# ProProject_Shield_na_MachXO3_devboard_20.net
KiCad netlist of a schematic drawn in EasyEDA Pro
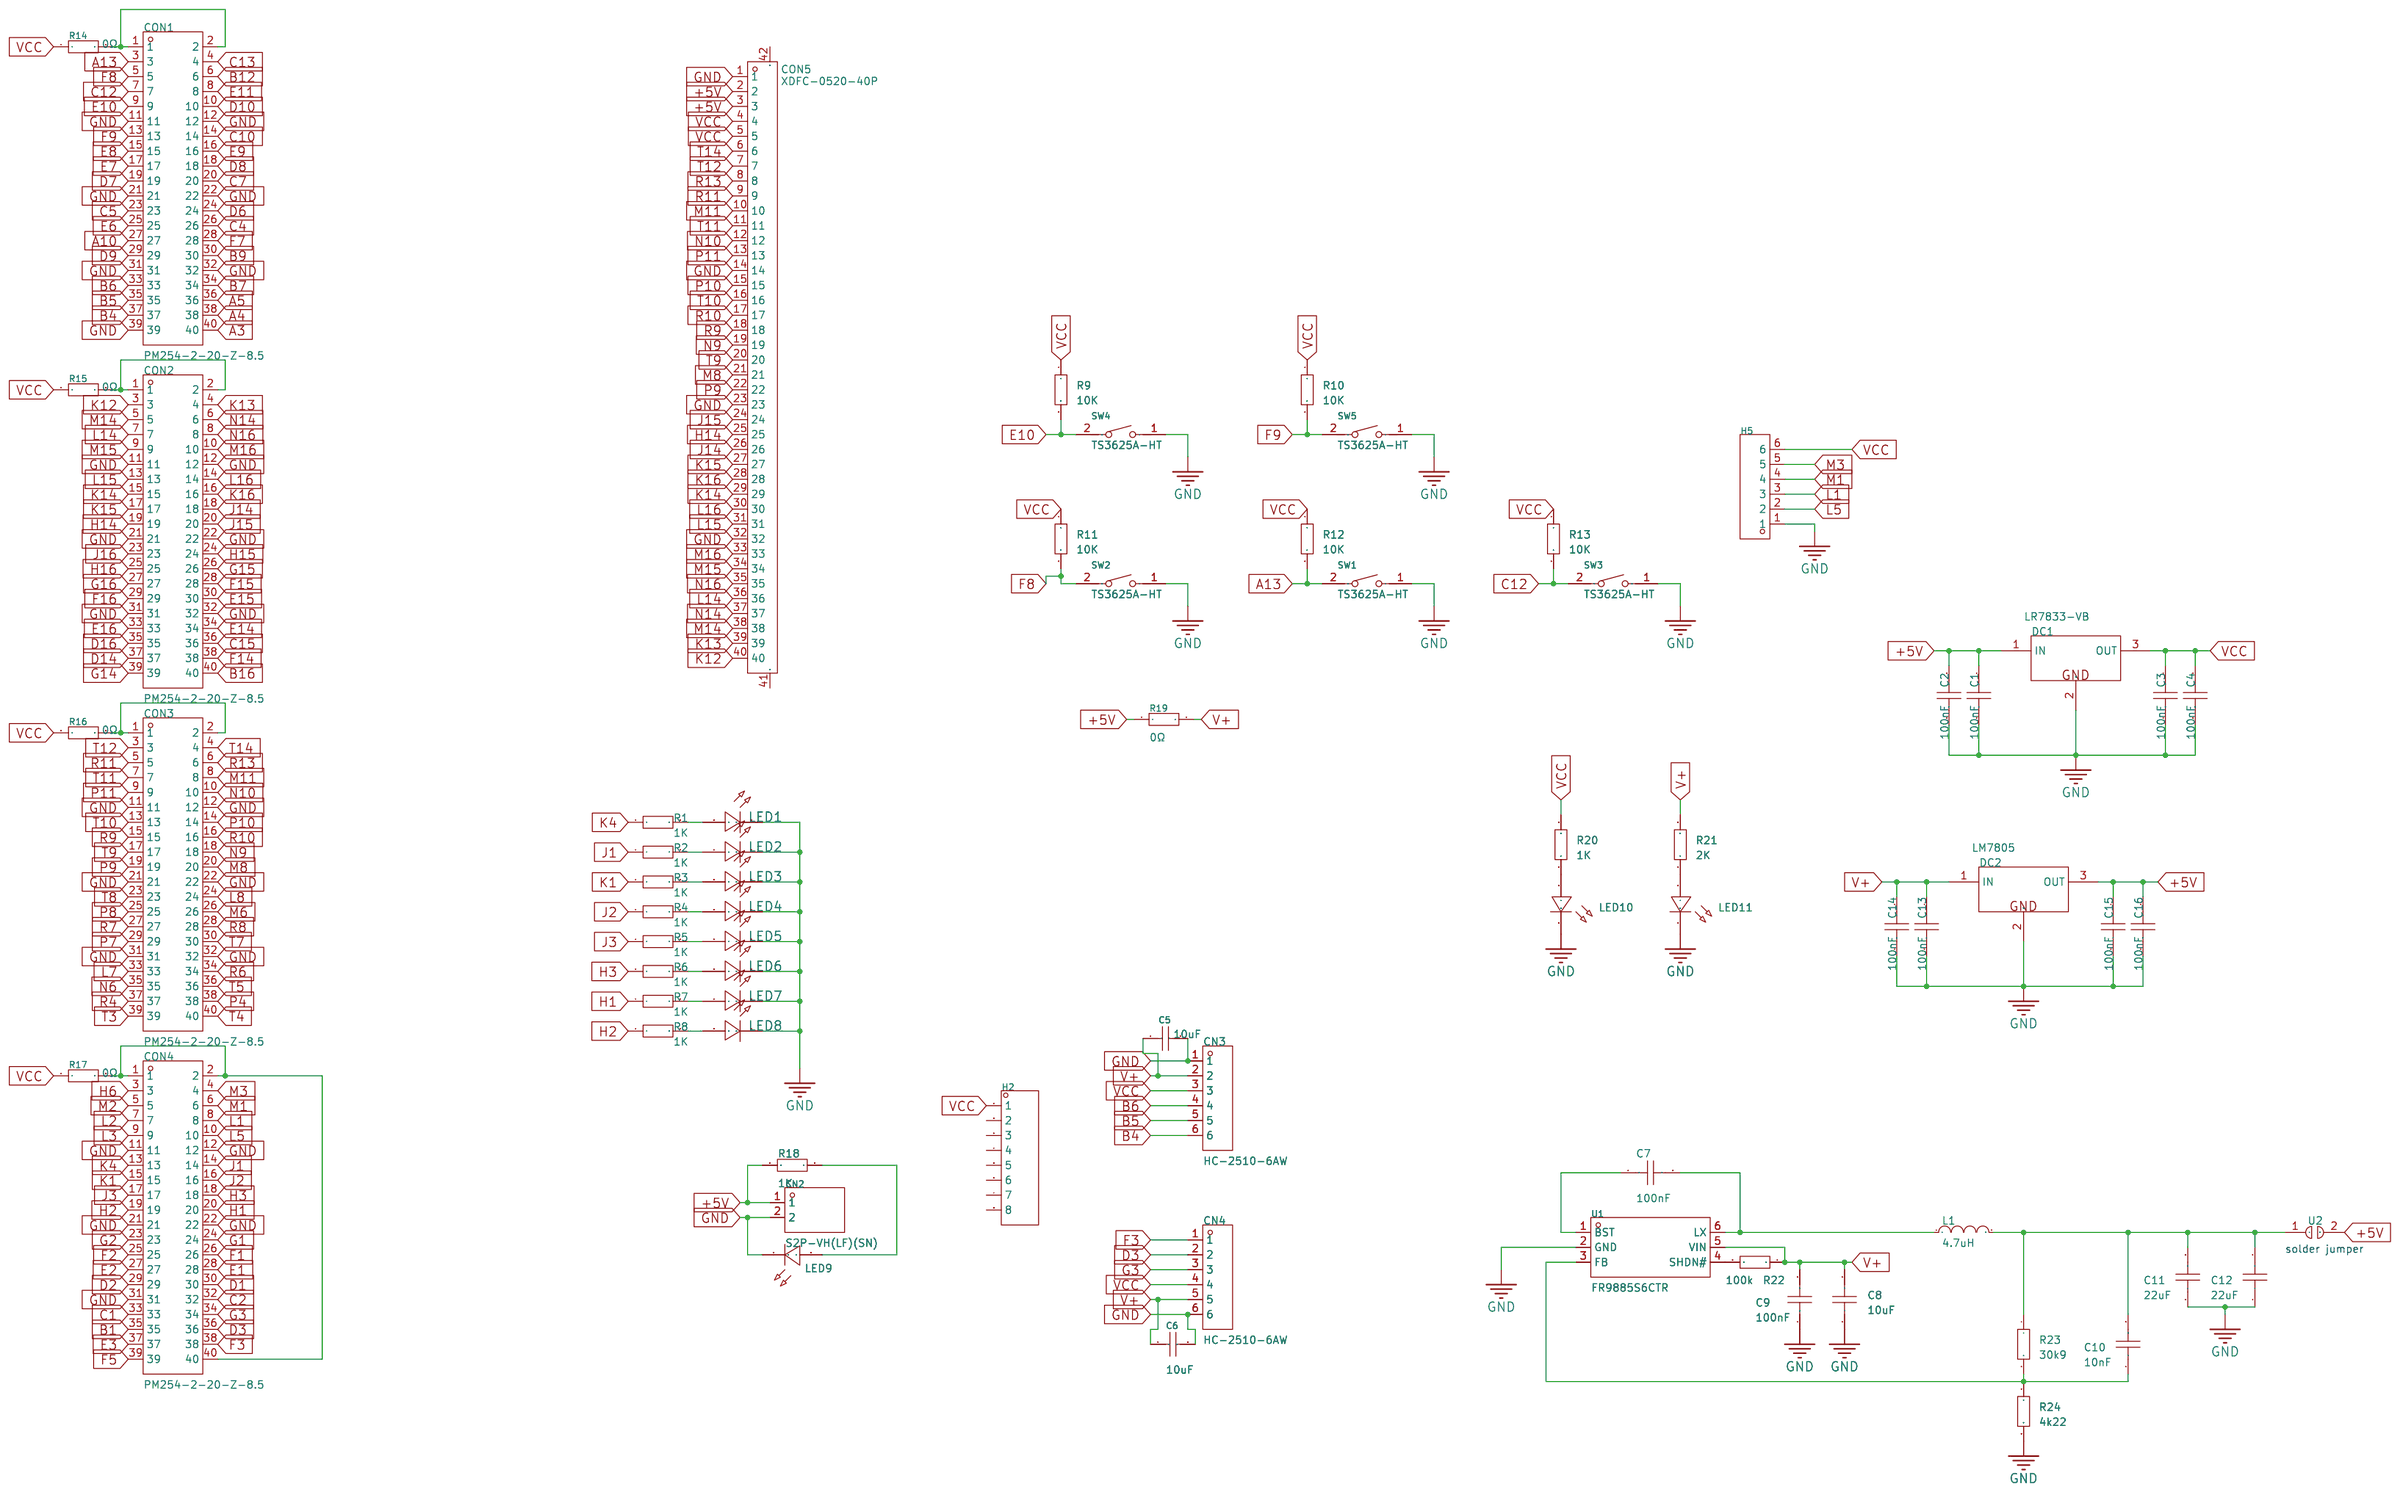
[diagram p0: schematic sheet]

(export (version "E")
  (design (tool "Eeschema 10.0.6"))
  (components
    (comp (ref "C1")
      (value "100nF")
      (footprint "easyedapro:C0805")
      (libsource (lib "easyedapro") (part "CAP"))
    )
    (comp (ref "C2")
      (value "100nF")
      (footprint "easyedapro:C0805")
      (libsource (lib "easyedapro") (part "CAP"))
    )
    (comp (ref "C3")
      (value "100nF")
      (footprint "easyedapro:C0805")
      (libsource (lib "easyedapro") (part "CAP"))
    )
    (comp (ref "C4")
      (value "100nF")
      (footprint "easyedapro:C0805")
      (libsource (lib "easyedapro") (part "CAP"))
    )
    (comp (ref "C5")
      (value "10uF")
      (footprint "easyedapro:C1206")
      (fields
        (field (name "Manufacturer Part") "CL31A107MQHNNNE")
        (field (name "Manufacturer") "SAMSUNG(三星)")
      )
      (libsource (lib "easyedapro") (part "CL31A107MQHNNNE"))
    )
    (comp (ref "C6")
      (value "10uF")
      (footprint "easyedapro:C1206")
      (fields
        (field (name "Manufacturer Part") "CL31A107MQHNNNE")
        (field (name "Manufacturer") "SAMSUNG(三星)")
      )
      (libsource (lib "easyedapro") (part "CL31A107MQHNNNE"))
    )
    (comp (ref "C7")
      (value "100nF")
      (footprint "easyedapro:C0805")
      (libsource (lib "easyedapro") (part "CAP"))
    )
    (comp (ref "C8")
      (value "10uF")
      (footprint "easyedapro:C0805")
      (libsource (lib "easyedapro") (part "CAP"))
    )
    (comp (ref "C9")
      (value "100nF")
      (footprint "easyedapro:C0805")
      (libsource (lib "easyedapro") (part "CAP"))
    )
    (comp (ref "C10")
      (value "10nF")
      (footprint "easyedapro:C0805")
      (libsource (lib "easyedapro") (part "CAP"))
    )
    (comp (ref "C11")
      (value "22uF")
      (footprint "easyedapro:C0805")
      (libsource (lib "easyedapro") (part "CAP"))
    )
    (comp (ref "C12")
      (value "22uF")
      (footprint "easyedapro:C0805")
      (libsource (lib "easyedapro") (part "CAP"))
    )
    (comp (ref "C13")
      (value "100nF")
      (footprint "easyedapro:C0805")
      (libsource (lib "easyedapro") (part "CAP"))
    )
    (comp (ref "C14")
      (value "100nF")
      (footprint "easyedapro:C0805")
      (libsource (lib "easyedapro") (part "CAP"))
    )
    (comp (ref "C15")
      (value "100nF")
      (footprint "easyedapro:C0805")
      (libsource (lib "easyedapro") (part "CAP"))
    )
    (comp (ref "C16")
      (value "100nF")
      (footprint "easyedapro:C0805")
      (libsource (lib "easyedapro") (part "CAP"))
    )
    (comp (ref "CN2")
      (value "S2P-VH(LF)(SN)")
      (footprint "easyedapro:CONN-TH_S2P-VH-LF-SN")
      (fields (field (name "Manufacturer") "JST"))
      (libsource (lib "easyedapro") (part "S2P-VH (LF)(SN)"))
    )
    (comp (ref "CN3")
      (value "HC-2510-6AW")
      (footprint "easyedapro:CONN-TH_6P-P2.54_HCTL_HC-2510-6AW")
      (fields (field (name "Manufacturer") "HCTL(华灿天禄)"))
      (libsource (lib "easyedapro") (part "HC-2510-6AW"))
    )
    (comp (ref "CN4")
      (value "HC-2510-6AW")
      (footprint "easyedapro:CONN-TH_6P-P2.54_HCTL_HC-2510-6AW")
      (fields (field (name "Manufacturer") "HCTL(华灿天禄)"))
      (libsource (lib "easyedapro") (part "HC-2510-6AW"))
    )
    (comp (ref "CON1")
      (value "PM254-2-20-Z-8.5")
      (footprint "easyedapro:HDR-TH_40P-P2.54-V-F-R2-C20-S2.54")
      (fields (field (name "Manufacturer") "HCTL(华灿天禄)"))
      (libsource (lib "easyedapro") (part "PM254-2-20-Z-8.5"))
    )
    (comp (ref "CON2")
      (value "PM254-2-20-Z-8.5")
      (footprint "easyedapro:HDR-TH_40P-P2.54-V-F-R2-C20-S2.54")
      (fields (field (name "Manufacturer") "HCTL(华灿天禄)"))
      (libsource (lib "easyedapro") (part "PM254-2-20-Z-8.5"))
    )
    (comp (ref "CON3")
      (value "PM254-2-20-Z-8.5")
      (footprint "easyedapro:HDR-TH_40P-P2.54-V-F-R2-C20-S2.54")
      (fields (field (name "Manufacturer") "HCTL(华灿天禄)"))
      (libsource (lib "easyedapro") (part "PM254-2-20-Z-8.5"))
    )
    (comp (ref "CON4")
      (value "PM254-2-20-Z-8.5")
      (footprint "easyedapro:HDR-TH_40P-P2.54-V-F-R2-C20-S2.54")
      (fields (field (name "Manufacturer") "HCTL(华灿天禄)"))
      (libsource (lib "easyedapro") (part "PM254-2-20-Z-8.5"))
    )
    (comp (ref "CON5")
      (value "XDFC-0520-40P")
      (footprint "easyedapro:FPC-SMD_40P-P0.50_XDFC-0520-40P")
      (fields (field (name "Manufacturer") "LX(连欣科技)"))
      (libsource (lib "easyedapro") (part "XDFC-0520-40P"))
    )
    (comp (ref "DC1")
      (value "LR7833-VB")
      (footprint "easyedapro:TO-252-2_L6.5-W6.1-P4.58-LS10.0-TL")
      (fields (field (name "Manufacturer") "VBsemi(微碧半导体)"))
      (libsource (lib "easyedapro") (part "L78M05ABDT-TR"))
    )
    (comp (ref "DC2")
      (value "LM7805")
      (footprint "easyedapro:TO-252-2_L6.5-W6.1-P4.58-LS10.0-TL")
      (fields (field (name "Manufacturer") "HGSEMI(华冠)"))
      (libsource (lib "easyedapro") (part "L78M05ABDT-TR"))
    )
    (comp (ref "H2")
      (value "~")
      (footprint "easyedapro:HDR-TH_8P-P2.54-V-M")
      (libsource (lib "easyedapro") (part "Header-Male-2.54_1x8"))
    )
    (comp (ref "H5")
      (value "~")
      (footprint "easyedapro:HDR-TH_6P-P2.54-V-F")
      (libsource (lib "easyedapro") (part "Header-Female-2.54_1x6"))
    )
    (comp (ref "L1")
      (value "4.7uH")
      (footprint "easyedapro:L0402")
      (libsource (lib "easyedapro") (part "电感"))
    )
    (comp (ref "LED1")
      (value "~")
      (footprint "easyedapro:LED0805-RD_GREEN")
      (libsource (lib "easyedapro") (part "LED_R"))
    )
    (comp (ref "LED2")
      (value "~")
      (footprint "easyedapro:LED0805-RD_GREEN")
      (libsource (lib "easyedapro") (part "LED_R"))
    )
    (comp (ref "LED3")
      (value "~")
      (footprint "easyedapro:LED0805-RD_GREEN")
      (libsource (lib "easyedapro") (part "LED_R"))
    )
    (comp (ref "LED4")
      (value "~")
      (footprint "easyedapro:LED0805-RD_GREEN")
      (libsource (lib "easyedapro") (part "LED_R"))
    )
    (comp (ref "LED5")
      (value "~")
      (footprint "easyedapro:LED0805-RD_GREEN")
      (libsource (lib "easyedapro") (part "LED_R"))
    )
    (comp (ref "LED6")
      (value "~")
      (footprint "easyedapro:LED0805-RD_GREEN")
      (libsource (lib "easyedapro") (part "LED_R"))
    )
    (comp (ref "LED7")
      (value "~")
      (footprint "easyedapro:LED0805-RD_GREEN")
      (libsource (lib "easyedapro") (part "LED_R"))
    )
    (comp (ref "LED8")
      (value "~")
      (footprint "easyedapro:LED0805-RD_GREEN")
      (libsource (lib "easyedapro") (part "LED_R"))
    )
    (comp (ref "LED9")
      (value "~")
      (footprint "easyedapro:LED0805-RD_GREEN")
      (libsource (lib "easyedapro") (part "LED_G"))
    )
    (comp (ref "LED10")
      (value "~")
      (footprint "easyedapro:LED0805-RD_GREEN")
      (libsource (lib "easyedapro") (part "LED_B"))
    )
    (comp (ref "LED11")
      (value "~")
      (footprint "easyedapro:LED0805-RD_GREEN")
      (libsource (lib "easyedapro") (part "LED_G"))
    )
    (comp (ref "R1") (value "1K") (footprint "easyedapro:R0201") (libsource (lib "easyedapro") (part "Res")))
    (comp (ref "R2") (value "1K") (footprint "easyedapro:R0201") (libsource (lib "easyedapro") (part "Res")))
    (comp (ref "R3") (value "1K") (footprint "easyedapro:R0201") (libsource (lib "easyedapro") (part "Res")))
    (comp (ref "R4") (value "1K") (footprint "easyedapro:R0201") (libsource (lib "easyedapro") (part "Res")))
    (comp (ref "R5") (value "1K") (footprint "easyedapro:R0201") (libsource (lib "easyedapro") (part "Res")))
    (comp (ref "R6") (value "1K") (footprint "easyedapro:R0201") (libsource (lib "easyedapro") (part "Res")))
    (comp (ref "R7") (value "1K") (footprint "easyedapro:R0201") (libsource (lib "easyedapro") (part "Res")))
    (comp (ref "R8") (value "1K") (footprint "easyedapro:R0201") (libsource (lib "easyedapro") (part "Res")))
    (comp (ref "R9") (value "10K") (footprint "easyedapro:R0201") (libsource (lib "easyedapro") (part "Res")))
    (comp (ref "R10")
      (value "10K")
      (footprint "easyedapro:R0201")
      (libsource (lib "easyedapro") (part "Res"))
    )
    (comp (ref "R11")
      (value "10K")
      (footprint "easyedapro:R0201")
      (libsource (lib "easyedapro") (part "Res"))
    )
    (comp (ref "R12")
      (value "10K")
      (footprint "easyedapro:R0201")
      (libsource (lib "easyedapro") (part "Res"))
    )
    (comp (ref "R13")
      (value "10K")
      (footprint "easyedapro:R0201")
      (libsource (lib "easyedapro") (part "Res"))
    )
    (comp (ref "R14")
      (value "0Ω")
      (footprint "easyedapro:R0805")
      (fields
        (field (name "Manufacturer Part") "0805W8F0000T5E")
        (field (name "Manufacturer") "UNI-ROYAL(厚声)")
      )
      (libsource (lib "easyedapro") (part "0805W8F0000T5E"))
    )
    (comp (ref "R15")
      (value "0Ω")
      (footprint "easyedapro:R0805")
      (fields
        (field (name "Manufacturer Part") "0805W8F0000T5E")
        (field (name "Manufacturer") "UNI-ROYAL(厚声)")
      )
      (libsource (lib "easyedapro") (part "0805W8F0000T5E"))
    )
    (comp (ref "R16")
      (value "0Ω")
      (footprint "easyedapro:R0805")
      (fields
        (field (name "Manufacturer Part") "0805W8F0000T5E")
        (field (name "Manufacturer") "UNI-ROYAL(厚声)")
      )
      (libsource (lib "easyedapro") (part "0805W8F0000T5E"))
    )
    (comp (ref "R17")
      (value "0Ω")
      (footprint "easyedapro:R0805")
      (fields
        (field (name "Manufacturer Part") "0805W8F0000T5E")
        (field (name "Manufacturer") "UNI-ROYAL(厚声)")
      )
      (libsource (lib "easyedapro") (part "0805W8F0000T5E"))
    )
    (comp (ref "R18") (value "1K") (footprint "easyedapro:R0201") (libsource (lib "easyedapro") (part "Res")))
    (comp (ref "R19")
      (value "0Ω")
      (footprint "easyedapro:R0805")
      (fields
        (field (name "Manufacturer Part") "0805W8F0000T5E")
        (field (name "Manufacturer") "UNI-ROYAL(厚声)")
      )
      (libsource (lib "easyedapro") (part "0805W8F0000T5E"))
    )
    (comp (ref "R20") (value "1K") (footprint "easyedapro:R0201") (libsource (lib "easyedapro") (part "Res")))
    (comp (ref "R21") (value "2K") (footprint "easyedapro:R0201") (libsource (lib "easyedapro") (part "Res")))
    (comp (ref "R22")
      (value "100k")
      (footprint "easyedapro:R0201")
      (libsource (lib "easyedapro") (part "Res"))
    )
    (comp (ref "R23")
      (value "30k9")
      (footprint "easyedapro:R0201")
      (libsource (lib "easyedapro") (part "Res"))
    )
    (comp (ref "R24")
      (value "4k22")
      (footprint "easyedapro:R0201")
      (libsource (lib "easyedapro") (part "Res"))
    )
    (comp (ref "SW1")
      (value "TS3625A-HT")
      (footprint "easyedapro:SW-SMD_L6.1-W3.7-LS7.9")
      (fields (field (name "Manufacturer") "SHOU HAN(首韩)"))
      (libsource (lib "easyedapro") (part "TS3625A-HT"))
    )
    (comp (ref "SW2")
      (value "TS3625A-HT")
      (footprint "easyedapro:SW-SMD_L6.1-W3.7-LS7.9")
      (fields (field (name "Manufacturer") "SHOU HAN(首韩)"))
      (libsource (lib "easyedapro") (part "TS3625A-HT"))
    )
    (comp (ref "SW3")
      (value "TS3625A-HT")
      (footprint "easyedapro:SW-SMD_L6.1-W3.7-LS7.9")
      (fields (field (name "Manufacturer") "SHOU HAN(首韩)"))
      (libsource (lib "easyedapro") (part "TS3625A-HT"))
    )
    (comp (ref "SW4")
      (value "TS3625A-HT")
      (footprint "easyedapro:SW-SMD_L6.1-W3.7-LS7.9")
      (fields (field (name "Manufacturer") "SHOU HAN(首韩)"))
      (libsource (lib "easyedapro") (part "TS3625A-HT"))
    )
    (comp (ref "SW5")
      (value "TS3625A-HT")
      (footprint "easyedapro:SW-SMD_L6.1-W3.7-LS7.9")
      (fields (field (name "Manufacturer") "SHOU HAN(首韩)"))
      (libsource (lib "easyedapro") (part "TS3625A-HT"))
    )
    (comp (ref "U1")
      (value "FR9885S6CTR")
      (footprint "easyedapro:SOT-23-6_L2.9-W1.6-P0.95-LS2.8-BR")
      (fields (field (name "Manufacturer") "FITIPOWER(天钰)"))
      (libsource (lib "easyedapro") (part "FR9885S6CTR"))
    )
    (comp (ref "U2")
      (value "~")
      (footprint "easyedapro:Jumper")
      (libsource (lib "easyedapro") (part "Jumper"))
    )
  )
  (nets
    (net (code "1") (name "+5V") (class "Default")
      (node (ref "C1") (pin "1") (pinfunction "1_1") (pintype "input"))
      (node (ref "C15") (pin "1") (pinfunction "1_1") (pintype "input"))
      (node (ref "C16") (pin "1") (pinfunction "1_1") (pintype "input"))
      (node (ref "C2") (pin "1") (pinfunction "1_1") (pintype "input"))
      (node (ref "CN2") (pin "1") (pinfunction "1_1") (pintype "input"))
      (node (ref "CON5") (pin "2") (pinfunction "2_2") (pintype "unspecified"))
      (node (ref "CON5") (pin "3") (pinfunction "3_3") (pintype "unspecified"))
      (node (ref "DC1") (pin "1") (pinfunction "IN_1") (pintype "unspecified"))
      (node (ref "DC2") (pin "3") (pinfunction "OUT_3") (pintype "unspecified"))
      (node (ref "R18") (pin "1") (pinfunction "1_1") (pintype "input"))
      (node (ref "R19") (pin "1") (pinfunction "1_1") (pintype "input"))
      (node (ref "U2") (pin "2") (pinfunction "2_2") (pintype "input"))
    )
    (net (code "2") (name "A3") (class "Default")
      (node (ref "CON1") (pin "40") (pinfunction "40_40") (pintype "unspecified"))
    )
    (net (code "3") (name "A4") (class "Default")
      (node (ref "CON1") (pin "38") (pinfunction "38_38") (pintype "unspecified"))
    )
    (net (code "4") (name "A5") (class "Default")
      (node (ref "CON1") (pin "36") (pinfunction "36_36") (pintype "unspecified"))
    )
    (net (code "5") (name "A10") (class "Default")
      (node (ref "CON1") (pin "27") (pinfunction "27_27") (pintype "unspecified"))
    )
    (net (code "6") (name "A13") (class "Default")
      (node (ref "CON1") (pin "3") (pinfunction "3_3") (pintype "unspecified"))
      (node (ref "R12") (pin "2") (pinfunction "2_2") (pintype "input"))
      (node (ref "SW1") (pin "2") (pinfunction "B_2") (pintype "input"))
    )
    (net (code "7") (name "B1") (class "Default")
      (node (ref "CON4") (pin "35") (pinfunction "35_35") (pintype "unspecified"))
    )
    (net (code "8") (name "B4") (class "Default")
      (node (ref "CN3") (pin "6") (pinfunction "6_6") (pintype "unspecified"))
      (node (ref "CON1") (pin "37") (pinfunction "37_37") (pintype "unspecified"))
    )
    (net (code "9") (name "B5") (class "Default")
      (node (ref "CN3") (pin "5") (pinfunction "5_5") (pintype "unspecified"))
      (node (ref "CON1") (pin "35") (pinfunction "35_35") (pintype "unspecified"))
    )
    (net (code "10") (name "B6") (class "Default")
      (node (ref "CN3") (pin "4") (pinfunction "4_4") (pintype "unspecified"))
      (node (ref "CON1") (pin "33") (pinfunction "33_33") (pintype "unspecified"))
    )
    (net (code "11") (name "B7") (class "Default")
      (node (ref "CON1") (pin "34") (pinfunction "34_34") (pintype "unspecified"))
    )
    (net (code "12") (name "B9") (class "Default")
      (node (ref "CON1") (pin "30") (pinfunction "30_30") (pintype "unspecified"))
    )
    (net (code "13") (name "B12") (class "Default")
      (node (ref "CON1") (pin "6") (pinfunction "6_6") (pintype "unspecified"))
    )
    (net (code "14") (name "B16") (class "Default")
      (node (ref "CON2") (pin "40") (pinfunction "40_40") (pintype "unspecified"))
    )
    (net (code "15") (name "C1") (class "Default")
      (node (ref "CON4") (pin "33") (pinfunction "33_33") (pintype "unspecified"))
    )
    (net (code "16") (name "C2") (class "Default")
      (node (ref "CON4") (pin "32") (pinfunction "32_32") (pintype "unspecified"))
    )
    (net (code "17") (name "C4") (class "Default")
      (node (ref "CON1") (pin "26") (pinfunction "26_26") (pintype "unspecified"))
    )
    (net (code "18") (name "C5") (class "Default")
      (node (ref "CON1") (pin "23") (pinfunction "23_23") (pintype "unspecified"))
    )
    (net (code "19") (name "C7") (class "Default")
      (node (ref "CON1") (pin "20") (pinfunction "20_20") (pintype "unspecified"))
    )
    (net (code "20") (name "C10") (class "Default")
      (node (ref "CON1") (pin "14") (pinfunction "14_14") (pintype "unspecified"))
    )
    (net (code "21") (name "C12") (class "Default")
      (node (ref "CON1") (pin "7") (pinfunction "7_7") (pintype "unspecified"))
      (node (ref "R13") (pin "2") (pinfunction "2_2") (pintype "input"))
      (node (ref "SW3") (pin "2") (pinfunction "B_2") (pintype "input"))
    )
    (net (code "22") (name "C13") (class "Default")
      (node (ref "CON1") (pin "4") (pinfunction "4_4") (pintype "unspecified"))
    )
    (net (code "23") (name "C15") (class "Default")
      (node (ref "CON2") (pin "36") (pinfunction "36_36") (pintype "unspecified"))
    )
    (net (code "24") (name "D1") (class "Default")
      (node (ref "CON4") (pin "30") (pinfunction "30_30") (pintype "unspecified"))
    )
    (net (code "25") (name "D2") (class "Default")
      (node (ref "CON4") (pin "29") (pinfunction "29_29") (pintype "unspecified"))
    )
    (net (code "26") (name "D3") (class "Default")
      (node (ref "CN4") (pin "2") (pinfunction "2_2") (pintype "unspecified"))
      (node (ref "CON4") (pin "36") (pinfunction "36_36") (pintype "unspecified"))
    )
    (net (code "27") (name "D6") (class "Default")
      (node (ref "CON1") (pin "24") (pinfunction "24_24") (pintype "unspecified"))
    )
    (net (code "28") (name "D7") (class "Default")
      (node (ref "CON1") (pin "19") (pinfunction "19_19") (pintype "unspecified"))
    )
    (net (code "29") (name "D8") (class "Default")
      (node (ref "CON1") (pin "18") (pinfunction "18_18") (pintype "unspecified"))
    )
    (net (code "30") (name "D9") (class "Default")
      (node (ref "CON1") (pin "29") (pinfunction "29_29") (pintype "unspecified"))
    )
    (net (code "31") (name "D10") (class "Default")
      (node (ref "CON1") (pin "10") (pinfunction "10_10") (pintype "unspecified"))
    )
    (net (code "32") (name "D14") (class "Default")
      (node (ref "CON2") (pin "37") (pinfunction "37_37") (pintype "unspecified"))
    )
    (net (code "33") (name "D16") (class "Default")
      (node (ref "CON2") (pin "35") (pinfunction "35_35") (pintype "unspecified"))
    )
    (net (code "34") (name "E1") (class "Default")
      (node (ref "CON4") (pin "28") (pinfunction "28_28") (pintype "unspecified"))
    )
    (net (code "35") (name "E2") (class "Default")
      (node (ref "CON4") (pin "27") (pinfunction "27_27") (pintype "unspecified"))
    )
    (net (code "36") (name "E3") (class "Default")
      (node (ref "CON4") (pin "37") (pinfunction "37_37") (pintype "unspecified"))
    )
    (net (code "37") (name "E6") (class "Default")
      (node (ref "CON1") (pin "25") (pinfunction "25_25") (pintype "unspecified"))
    )
    (net (code "38") (name "E7") (class "Default")
      (node (ref "CON1") (pin "17") (pinfunction "17_17") (pintype "unspecified"))
    )
    (net (code "39") (name "E8") (class "Default")
      (node (ref "CON1") (pin "15") (pinfunction "15_15") (pintype "unspecified"))
    )
    (net (code "40") (name "E9") (class "Default")
      (node (ref "CON1") (pin "16") (pinfunction "16_16") (pintype "unspecified"))
    )
    (net (code "41") (name "E10") (class "Default")
      (node (ref "CON1") (pin "9") (pinfunction "9_9") (pintype "unspecified"))
      (node (ref "R9") (pin "2") (pinfunction "2_2") (pintype "input"))
      (node (ref "SW4") (pin "2") (pinfunction "B_2") (pintype "input"))
    )
    (net (code "42") (name "E11") (class "Default")
      (node (ref "CON1") (pin "8") (pinfunction "8_8") (pintype "unspecified"))
    )
    (net (code "43") (name "E14") (class "Default")
      (node (ref "CON2") (pin "34") (pinfunction "34_34") (pintype "unspecified"))
    )
    (net (code "44") (name "E15") (class "Default")
      (node (ref "CON2") (pin "30") (pinfunction "30_30") (pintype "unspecified"))
    )
    (net (code "45") (name "E16") (class "Default")
      (node (ref "CON2") (pin "33") (pinfunction "33_33") (pintype "unspecified"))
    )
    (net (code "46") (name "F1") (class "Default")
      (node (ref "CON4") (pin "26") (pinfunction "26_26") (pintype "unspecified"))
    )
    (net (code "47") (name "F2") (class "Default")
      (node (ref "CON4") (pin "25") (pinfunction "25_25") (pintype "unspecified"))
    )
    (net (code "48") (name "F3") (class "Default")
      (node (ref "CN4") (pin "1") (pinfunction "1_1") (pintype "unspecified"))
      (node (ref "CON4") (pin "38") (pinfunction "38_38") (pintype "unspecified"))
    )
    (net (code "49") (name "F5") (class "Default")
      (node (ref "CON4") (pin "39") (pinfunction "39_39") (pintype "unspecified"))
    )
    (net (code "50") (name "F7") (class "Default")
      (node (ref "CON1") (pin "28") (pinfunction "28_28") (pintype "unspecified"))
    )
    (net (code "51") (name "F8") (class "Default")
      (node (ref "CON1") (pin "5") (pinfunction "5_5") (pintype "unspecified"))
      (node (ref "R11") (pin "2") (pinfunction "2_2") (pintype "input"))
      (node (ref "SW2") (pin "2") (pinfunction "B_2") (pintype "input"))
    )
    (net (code "52") (name "F9") (class "Default")
      (node (ref "CON1") (pin "13") (pinfunction "13_13") (pintype "unspecified"))
      (node (ref "R10") (pin "2") (pinfunction "2_2") (pintype "input"))
      (node (ref "SW5") (pin "2") (pinfunction "B_2") (pintype "input"))
    )
    (net (code "53") (name "F14") (class "Default")
      (node (ref "CON2") (pin "38") (pinfunction "38_38") (pintype "unspecified"))
    )
    (net (code "54") (name "F15") (class "Default")
      (node (ref "CON2") (pin "28") (pinfunction "28_28") (pintype "unspecified"))
    )
    (net (code "55") (name "F16") (class "Default")
      (node (ref "CON2") (pin "29") (pinfunction "29_29") (pintype "unspecified"))
    )
    (net (code "56") (name "G1") (class "Default")
      (node (ref "CON4") (pin "24") (pinfunction "24_24") (pintype "unspecified"))
    )
    (net (code "57") (name "G2") (class "Default")
      (node (ref "CON4") (pin "23") (pinfunction "23_23") (pintype "unspecified"))
    )
    (net (code "58") (name "G3") (class "Default")
      (node (ref "CN4") (pin "3") (pinfunction "3_3") (pintype "unspecified"))
      (node (ref "CON4") (pin "34") (pinfunction "34_34") (pintype "unspecified"))
    )
    (net (code "59") (name "G14") (class "Default")
      (node (ref "CON2") (pin "39") (pinfunction "39_39") (pintype "unspecified"))
    )
    (net (code "60") (name "G15") (class "Default")
      (node (ref "CON2") (pin "26") (pinfunction "26_26") (pintype "unspecified"))
    )
    (net (code "61") (name "G16") (class "Default")
      (node (ref "CON2") (pin "27") (pinfunction "27_27") (pintype "unspecified"))
    )
    (net (code "62") (name "GND") (class "Default")
      (node (ref "C1") (pin "2") (pinfunction "2_2") (pintype "input"))
      (node (ref "C11") (pin "1") (pinfunction "1_1") (pintype "input"))
      (node (ref "C12") (pin "1") (pinfunction "1_1") (pintype "input"))
      (node (ref "C13") (pin "2") (pinfunction "2_2") (pintype "input"))
      (node (ref "C14") (pin "2") (pinfunction "2_2") (pintype "input"))
      (node (ref "C15") (pin "2") (pinfunction "2_2") (pintype "input"))
      (node (ref "C16") (pin "2") (pinfunction "2_2") (pintype "input"))
      (node (ref "C2") (pin "2") (pinfunction "2_2") (pintype "input"))
      (node (ref "C3") (pin "2") (pinfunction "2_2") (pintype "input"))
      (node (ref "C4") (pin "2") (pinfunction "2_2") (pintype "input"))
      (node (ref "C5") (pin "2") (pinfunction "2_2") (pintype "input"))
      (node (ref "C6") (pin "2") (pinfunction "2_2") (pintype "input"))
      (node (ref "C8") (pin "1") (pinfunction "1_1") (pintype "input"))
      (node (ref "C9") (pin "1") (pinfunction "1_1") (pintype "input"))
      (node (ref "CN2") (pin "2") (pinfunction "2_2") (pintype "input"))
      (node (ref "CN3") (pin "1") (pinfunction "1_1") (pintype "unspecified"))
      (node (ref "CN4") (pin "6") (pinfunction "6_6") (pintype "unspecified"))
      (node (ref "CON1") (pin "11") (pinfunction "11_11") (pintype "unspecified"))
      (node (ref "CON1") (pin "12") (pinfunction "12_12") (pintype "unspecified"))
      (node (ref "CON1") (pin "21") (pinfunction "21_21") (pintype "unspecified"))
      (node (ref "CON1") (pin "22") (pinfunction "22_22") (pintype "unspecified"))
      (node (ref "CON1") (pin "31") (pinfunction "31_31") (pintype "unspecified"))
      (node (ref "CON1") (pin "32") (pinfunction "32_32") (pintype "unspecified"))
      (node (ref "CON1") (pin "39") (pinfunction "39_39") (pintype "unspecified"))
      (node (ref "CON2") (pin "11") (pinfunction "11_11") (pintype "unspecified"))
      (node (ref "CON2") (pin "12") (pinfunction "12_12") (pintype "unspecified"))
      (node (ref "CON2") (pin "21") (pinfunction "21_21") (pintype "unspecified"))
      (node (ref "CON2") (pin "22") (pinfunction "22_22") (pintype "unspecified"))
      (node (ref "CON2") (pin "31") (pinfunction "31_31") (pintype "unspecified"))
      (node (ref "CON2") (pin "32") (pinfunction "32_32") (pintype "unspecified"))
      (node (ref "CON3") (pin "11") (pinfunction "11_11") (pintype "unspecified"))
      (node (ref "CON3") (pin "12") (pinfunction "12_12") (pintype "unspecified"))
      (node (ref "CON3") (pin "21") (pinfunction "21_21") (pintype "unspecified"))
      (node (ref "CON3") (pin "22") (pinfunction "22_22") (pintype "unspecified"))
      (node (ref "CON3") (pin "31") (pinfunction "31_31") (pintype "unspecified"))
      (node (ref "CON3") (pin "32") (pinfunction "32_32") (pintype "unspecified"))
      (node (ref "CON4") (pin "11") (pinfunction "11_11") (pintype "unspecified"))
      (node (ref "CON4") (pin "12") (pinfunction "12_12") (pintype "unspecified"))
      (node (ref "CON4") (pin "21") (pinfunction "21_21") (pintype "unspecified"))
      (node (ref "CON4") (pin "22") (pinfunction "22_22") (pintype "unspecified"))
      (node (ref "CON4") (pin "31") (pinfunction "31_31") (pintype "unspecified"))
      (node (ref "CON5") (pin "1") (pinfunction "1_1") (pintype "unspecified"))
      (node (ref "CON5") (pin "14") (pinfunction "14_14") (pintype "unspecified"))
      (node (ref "CON5") (pin "23") (pinfunction "23_23") (pintype "unspecified"))
      (node (ref "CON5") (pin "32") (pinfunction "32_32") (pintype "unspecified"))
      (node (ref "DC1") (pin "2") (pinfunction "GND_2") (pintype "unspecified"))
      (node (ref "DC2") (pin "2") (pinfunction "GND_2") (pintype "unspecified"))
      (node (ref "H5") (pin "1") (pinfunction "1_1") (pintype "input"))
      (node (ref "LED1") (pin "2") (pinfunction "C_2") (pintype "input"))
      (node (ref "LED10") (pin "1") (pinfunction "C_1") (pintype "input"))
      (node (ref "LED11") (pin "1") (pinfunction "C_1") (pintype "input"))
      (node (ref "LED2") (pin "2") (pinfunction "C_2") (pintype "input"))
      (node (ref "LED3") (pin "2") (pinfunction "C_2") (pintype "input"))
      (node (ref "LED4") (pin "2") (pinfunction "C_2") (pintype "input"))
      (node (ref "LED5") (pin "2") (pinfunction "C_2") (pintype "input"))
      (node (ref "LED6") (pin "2") (pinfunction "C_2") (pintype "input"))
      (node (ref "LED7") (pin "2") (pinfunction "C_2") (pintype "input"))
      (node (ref "LED8") (pin "2") (pinfunction "C_2") (pintype "input"))
      (node (ref "LED9") (pin "1") (pinfunction "C_1") (pintype "input"))
      (node (ref "R24") (pin "2") (pinfunction "2_2") (pintype "input"))
      (node (ref "SW1") (pin "1") (pinfunction "A_1") (pintype "input"))
      (node (ref "SW2") (pin "1") (pinfunction "A_1") (pintype "input"))
      (node (ref "SW3") (pin "1") (pinfunction "A_1") (pintype "input"))
      (node (ref "SW4") (pin "1") (pinfunction "A_1") (pintype "input"))
      (node (ref "SW5") (pin "1") (pinfunction "A_1") (pintype "input"))
      (node (ref "U1") (pin "2") (pinfunction "GND_2") (pintype "input"))
    )
    (net (code "63") (name "H1") (class "Default")
      (node (ref "CON4") (pin "20") (pinfunction "20_20") (pintype "unspecified"))
      (node (ref "R7") (pin "1") (pinfunction "1_1") (pintype "input"))
    )
    (net (code "64") (name "H2") (class "Default")
      (node (ref "CON4") (pin "19") (pinfunction "19_19") (pintype "unspecified"))
      (node (ref "R8") (pin "1") (pinfunction "1_1") (pintype "input"))
    )
    (net (code "65") (name "H3") (class "Default")
      (node (ref "CON4") (pin "18") (pinfunction "18_18") (pintype "unspecified"))
      (node (ref "R6") (pin "1") (pinfunction "1_1") (pintype "input"))
    )
    (net (code "66") (name "H6") (class "Default")
      (node (ref "CON4") (pin "3") (pinfunction "3_3") (pintype "unspecified"))
    )
    (net (code "67") (name "H14") (class "Default")
      (node (ref "CON2") (pin "19") (pinfunction "19_19") (pintype "unspecified"))
      (node (ref "CON5") (pin "25") (pinfunction "25_25") (pintype "unspecified"))
    )
    (net (code "68") (name "H15") (class "Default")
      (node (ref "CON2") (pin "24") (pinfunction "24_24") (pintype "unspecified"))
    )
    (net (code "69") (name "H16") (class "Default")
      (node (ref "CON2") (pin "25") (pinfunction "25_25") (pintype "unspecified"))
    )
    (net (code "70") (name "J1") (class "Default")
      (node (ref "CON4") (pin "14") (pinfunction "14_14") (pintype "unspecified"))
      (node (ref "R2") (pin "1") (pinfunction "1_1") (pintype "input"))
    )
    (net (code "71") (name "J2") (class "Default")
      (node (ref "CON4") (pin "16") (pinfunction "16_16") (pintype "unspecified"))
      (node (ref "R4") (pin "1") (pinfunction "1_1") (pintype "input"))
    )
    (net (code "72") (name "J3") (class "Default")
      (node (ref "CON4") (pin "17") (pinfunction "17_17") (pintype "unspecified"))
      (node (ref "R5") (pin "1") (pinfunction "1_1") (pintype "input"))
    )
    (net (code "73") (name "J14") (class "Default")
      (node (ref "CON2") (pin "18") (pinfunction "18_18") (pintype "unspecified"))
      (node (ref "CON5") (pin "26") (pinfunction "26_26") (pintype "unspecified"))
    )
    (net (code "74") (name "J15") (class "Default")
      (node (ref "CON2") (pin "20") (pinfunction "20_20") (pintype "unspecified"))
      (node (ref "CON5") (pin "24") (pinfunction "24_24") (pintype "unspecified"))
    )
    (net (code "75") (name "J16") (class "Default")
      (node (ref "CON2") (pin "23") (pinfunction "23_23") (pintype "unspecified"))
    )
    (net (code "76") (name "K1") (class "Default")
      (node (ref "CON4") (pin "15") (pinfunction "15_15") (pintype "unspecified"))
      (node (ref "R3") (pin "1") (pinfunction "1_1") (pintype "input"))
    )
    (net (code "77") (name "K4") (class "Default")
      (node (ref "CON4") (pin "13") (pinfunction "13_13") (pintype "unspecified"))
      (node (ref "R1") (pin "1") (pinfunction "1_1") (pintype "input"))
    )
    (net (code "78") (name "K12") (class "Default")
      (node (ref "CON2") (pin "3") (pinfunction "3_3") (pintype "unspecified"))
      (node (ref "CON5") (pin "40") (pinfunction "40_40") (pintype "unspecified"))
    )
    (net (code "79") (name "K13") (class "Default")
      (node (ref "CON2") (pin "4") (pinfunction "4_4") (pintype "unspecified"))
      (node (ref "CON5") (pin "39") (pinfunction "39_39") (pintype "unspecified"))
    )
    (net (code "80") (name "K14") (class "Default")
      (node (ref "CON2") (pin "15") (pinfunction "15_15") (pintype "unspecified"))
      (node (ref "CON5") (pin "29") (pinfunction "29_29") (pintype "unspecified"))
    )
    (net (code "81") (name "K15") (class "Default")
      (node (ref "CON2") (pin "17") (pinfunction "17_17") (pintype "unspecified"))
      (node (ref "CON5") (pin "27") (pinfunction "27_27") (pintype "unspecified"))
    )
    (net (code "82") (name "K16") (class "Default")
      (node (ref "CON2") (pin "16") (pinfunction "16_16") (pintype "unspecified"))
      (node (ref "CON5") (pin "28") (pinfunction "28_28") (pintype "unspecified"))
    )
    (net (code "83") (name "L1") (class "Default")
      (node (ref "CON4") (pin "8") (pinfunction "8_8") (pintype "unspecified"))
      (node (ref "H5") (pin "3") (pinfunction "3_3") (pintype "input"))
    )
    (net (code "84") (name "L2") (class "Default")
      (node (ref "CON4") (pin "7") (pinfunction "7_7") (pintype "unspecified"))
    )
    (net (code "85") (name "L3") (class "Default")
      (node (ref "CON4") (pin "9") (pinfunction "9_9") (pintype "unspecified"))
    )
    (net (code "86") (name "L5") (class "Default")
      (node (ref "CON4") (pin "10") (pinfunction "10_10") (pintype "unspecified"))
      (node (ref "H5") (pin "2") (pinfunction "2_2") (pintype "input"))
    )
    (net (code "87") (name "L7") (class "Default")
      (node (ref "CON3") (pin "33") (pinfunction "33_33") (pintype "unspecified"))
    )
    (net (code "88") (name "L8") (class "Default")
      (node (ref "CON3") (pin "24") (pinfunction "24_24") (pintype "unspecified"))
    )
    (net (code "89") (name "L14") (class "Default")
      (node (ref "CON2") (pin "7") (pinfunction "7_7") (pintype "unspecified"))
      (node (ref "CON5") (pin "36") (pinfunction "36_36") (pintype "unspecified"))
    )
    (net (code "90") (name "L15") (class "Default")
      (node (ref "CON2") (pin "13") (pinfunction "13_13") (pintype "unspecified"))
      (node (ref "CON5") (pin "31") (pinfunction "31_31") (pintype "unspecified"))
    )
    (net (code "91") (name "L16") (class "Default")
      (node (ref "CON2") (pin "14") (pinfunction "14_14") (pintype "unspecified"))
      (node (ref "CON5") (pin "30") (pinfunction "30_30") (pintype "unspecified"))
    )
    (net (code "92") (name "M1") (class "Default")
      (node (ref "CON4") (pin "6") (pinfunction "6_6") (pintype "unspecified"))
      (node (ref "H5") (pin "4") (pinfunction "4_4") (pintype "input"))
    )
    (net (code "93") (name "M2") (class "Default")
      (node (ref "CON4") (pin "5") (pinfunction "5_5") (pintype "unspecified"))
    )
    (net (code "94") (name "M3") (class "Default")
      (node (ref "CON4") (pin "4") (pinfunction "4_4") (pintype "unspecified"))
      (node (ref "H5") (pin "5") (pinfunction "5_5") (pintype "input"))
    )
    (net (code "95") (name "M6") (class "Default")
      (node (ref "CON3") (pin "26") (pinfunction "26_26") (pintype "unspecified"))
    )
    (net (code "96") (name "M8") (class "Default")
      (node (ref "CON3") (pin "20") (pinfunction "20_20") (pintype "unspecified"))
      (node (ref "CON5") (pin "21") (pinfunction "21_21") (pintype "unspecified"))
    )
    (net (code "97") (name "M11") (class "Default")
      (node (ref "CON3") (pin "8") (pinfunction "8_8") (pintype "unspecified"))
      (node (ref "CON5") (pin "10") (pinfunction "10_10") (pintype "unspecified"))
    )
    (net (code "98") (name "M14") (class "Default")
      (node (ref "CON2") (pin "5") (pinfunction "5_5") (pintype "unspecified"))
      (node (ref "CON5") (pin "38") (pinfunction "38_38") (pintype "unspecified"))
    )
    (net (code "99") (name "M15") (class "Default")
      (node (ref "CON2") (pin "9") (pinfunction "9_9") (pintype "unspecified"))
      (node (ref "CON5") (pin "34") (pinfunction "34_34") (pintype "unspecified"))
    )
    (net (code "100") (name "M16") (class "Default")
      (node (ref "CON2") (pin "10") (pinfunction "10_10") (pintype "unspecified"))
      (node (ref "CON5") (pin "33") (pinfunction "33_33") (pintype "unspecified"))
    )
    (net (code "101") (name "N6") (class "Default")
      (node (ref "CON3") (pin "35") (pinfunction "35_35") (pintype "unspecified"))
    )
    (net (code "102") (name "N9") (class "Default")
      (node (ref "CON3") (pin "18") (pinfunction "18_18") (pintype "unspecified"))
      (node (ref "CON5") (pin "19") (pinfunction "19_19") (pintype "unspecified"))
    )
    (net (code "103") (name "N10") (class "Default")
      (node (ref "CON3") (pin "10") (pinfunction "10_10") (pintype "unspecified"))
      (node (ref "CON5") (pin "12") (pinfunction "12_12") (pintype "unspecified"))
    )
    (net (code "104") (name "N14") (class "Default")
      (node (ref "CON2") (pin "6") (pinfunction "6_6") (pintype "unspecified"))
      (node (ref "CON5") (pin "37") (pinfunction "37_37") (pintype "unspecified"))
    )
    (net (code "105") (name "N16") (class "Default")
      (node (ref "CON2") (pin "8") (pinfunction "8_8") (pintype "unspecified"))
      (node (ref "CON5") (pin "35") (pinfunction "35_35") (pintype "unspecified"))
    )
    (net (code "106") (name "Net-(C10-Pad2)") (class "Default")
      (node (ref "C10") (pin "2") (pinfunction "2_2") (pintype "input"))
      (node (ref "C11") (pin "2") (pinfunction "2_2") (pintype "input"))
      (node (ref "C12") (pin "2") (pinfunction "2_2") (pintype "input"))
      (node (ref "L1") (pin "2") (pinfunction "2_2") (pintype "input"))
      (node (ref "R23") (pin "1") (pinfunction "1_1") (pintype "input"))
      (node (ref "U2") (pin "1") (pinfunction "1_1") (pintype "input"))
    )
    (net (code "107") (name "Net-(CON1-Pad1)") (class "Default")
      (node (ref "CON1") (pin "1") (pinfunction "1_1") (pintype "unspecified"))
      (node (ref "CON1") (pin "2") (pinfunction "2_2") (pintype "unspecified"))
      (node (ref "R14") (pin "2") (pinfunction "2_2") (pintype "input"))
    )
    (net (code "108") (name "Net-(CON2-Pad1)") (class "Default")
      (node (ref "CON2") (pin "1") (pinfunction "1_1") (pintype "unspecified"))
      (node (ref "CON2") (pin "2") (pinfunction "2_2") (pintype "unspecified"))
      (node (ref "R15") (pin "2") (pinfunction "2_2") (pintype "input"))
    )
    (net (code "109") (name "Net-(CON3-Pad1)") (class "Default")
      (node (ref "CON3") (pin "1") (pinfunction "1_1") (pintype "unspecified"))
      (node (ref "CON3") (pin "2") (pinfunction "2_2") (pintype "unspecified"))
      (node (ref "R16") (pin "2") (pinfunction "2_2") (pintype "input"))
    )
    (net (code "110") (name "Net-(CON4-Pad1)") (class "Default")
      (node (ref "CON4") (pin "1") (pinfunction "1_1") (pintype "unspecified"))
      (node (ref "CON4") (pin "2") (pinfunction "2_2") (pintype "unspecified"))
      (node (ref "CON4") (pin "40") (pinfunction "40_40") (pintype "unspecified"))
      (node (ref "R17") (pin "2") (pinfunction "2_2") (pintype "input"))
    )
    (net (code "111") (name "Net-(LED1-A)") (class "Default")
      (node (ref "LED1") (pin "1") (pinfunction "A_1") (pintype "input"))
      (node (ref "R1") (pin "2") (pinfunction "2_2") (pintype "input"))
    )
    (net (code "112") (name "Net-(LED2-A)") (class "Default")
      (node (ref "LED2") (pin "1") (pinfunction "A_1") (pintype "input"))
      (node (ref "R2") (pin "2") (pinfunction "2_2") (pintype "input"))
    )
    (net (code "113") (name "Net-(LED3-A)") (class "Default")
      (node (ref "LED3") (pin "1") (pinfunction "A_1") (pintype "input"))
      (node (ref "R3") (pin "2") (pinfunction "2_2") (pintype "input"))
    )
    (net (code "114") (name "Net-(LED4-A)") (class "Default")
      (node (ref "LED4") (pin "1") (pinfunction "A_1") (pintype "input"))
      (node (ref "R4") (pin "2") (pinfunction "2_2") (pintype "input"))
    )
    (net (code "115") (name "Net-(LED5-A)") (class "Default")
      (node (ref "LED5") (pin "1") (pinfunction "A_1") (pintype "input"))
      (node (ref "R5") (pin "2") (pinfunction "2_2") (pintype "input"))
    )
    (net (code "116") (name "Net-(LED6-A)") (class "Default")
      (node (ref "LED6") (pin "1") (pinfunction "A_1") (pintype "input"))
      (node (ref "R6") (pin "2") (pinfunction "2_2") (pintype "input"))
    )
    (net (code "117") (name "Net-(LED7-A)") (class "Default")
      (node (ref "LED7") (pin "1") (pinfunction "A_1") (pintype "input"))
      (node (ref "R7") (pin "2") (pinfunction "2_2") (pintype "input"))
    )
    (net (code "118") (name "Net-(LED8-A)") (class "Default")
      (node (ref "LED8") (pin "1") (pinfunction "A_1") (pintype "input"))
      (node (ref "R8") (pin "2") (pinfunction "2_2") (pintype "input"))
    )
    (net (code "119") (name "Net-(LED9-A)") (class "Default")
      (node (ref "LED9") (pin "2") (pinfunction "A_2") (pintype "input"))
      (node (ref "R18") (pin "2") (pinfunction "2_2") (pintype "input"))
    )
    (net (code "120") (name "Net-(LED10-A)") (class "Default")
      (node (ref "LED10") (pin "2") (pinfunction "A_2") (pintype "input"))
      (node (ref "R20") (pin "1") (pinfunction "1_1") (pintype "input"))
    )
    (net (code "121") (name "Net-(LED11-A)") (class "Default")
      (node (ref "LED11") (pin "2") (pinfunction "A_2") (pintype "input"))
      (node (ref "R21") (pin "1") (pinfunction "1_1") (pintype "input"))
    )
    (net (code "122") (name "Net-(U1-BST)") (class "Default")
      (node (ref "C7") (pin "1") (pinfunction "1_1") (pintype "input"))
      (node (ref "U1") (pin "1") (pinfunction "BST_1") (pintype "input"))
    )
    (net (code "123") (name "Net-(U1-FB)") (class "Default")
      (node (ref "C10") (pin "1") (pinfunction "1_1") (pintype "input"))
      (node (ref "R23") (pin "2") (pinfunction "2_2") (pintype "input"))
      (node (ref "R24") (pin "1") (pinfunction "1_1") (pintype "input"))
      (node (ref "U1") (pin "3") (pinfunction "FB_3") (pintype "input"))
    )
    (net (code "124") (name "Net-(U1-LX)") (class "Default")
      (node (ref "C7") (pin "2") (pinfunction "2_2") (pintype "input"))
      (node (ref "L1") (pin "1") (pinfunction "1_1") (pintype "input"))
      (node (ref "U1") (pin "6") (pinfunction "LX_6") (pintype "input"))
    )
    (net (code "125") (name "Net-(U1-SHDN#)") (class "Default")
      (node (ref "R22") (pin "2") (pinfunction "2_2") (pintype "input"))
      (node (ref "U1") (pin "4") (pinfunction "SHDN#_4") (pintype "input"))
    )
    (net (code "126") (name "P4") (class "Default")
      (node (ref "CON3") (pin "38") (pinfunction "38_38") (pintype "unspecified"))
    )
    (net (code "127") (name "P7") (class "Default")
      (node (ref "CON3") (pin "29") (pinfunction "29_29") (pintype "unspecified"))
    )
    (net (code "128") (name "P8") (class "Default")
      (node (ref "CON3") (pin "25") (pinfunction "25_25") (pintype "unspecified"))
    )
    (net (code "129") (name "P9") (class "Default")
      (node (ref "CON3") (pin "19") (pinfunction "19_19") (pintype "unspecified"))
      (node (ref "CON5") (pin "22") (pinfunction "22_22") (pintype "unspecified"))
    )
    (net (code "130") (name "P10") (class "Default")
      (node (ref "CON3") (pin "14") (pinfunction "14_14") (pintype "unspecified"))
      (node (ref "CON5") (pin "15") (pinfunction "15_15") (pintype "unspecified"))
    )
    (net (code "131") (name "P11") (class "Default")
      (node (ref "CON3") (pin "9") (pinfunction "9_9") (pintype "unspecified"))
      (node (ref "CON5") (pin "13") (pinfunction "13_13") (pintype "unspecified"))
    )
    (net (code "132") (name "R4") (class "Default")
      (node (ref "CON3") (pin "37") (pinfunction "37_37") (pintype "unspecified"))
    )
    (net (code "133") (name "R6") (class "Default")
      (node (ref "CON3") (pin "34") (pinfunction "34_34") (pintype "unspecified"))
    )
    (net (code "134") (name "R7") (class "Default")
      (node (ref "CON3") (pin "27") (pinfunction "27_27") (pintype "unspecified"))
    )
    (net (code "135") (name "R8") (class "Default")
      (node (ref "CON3") (pin "28") (pinfunction "28_28") (pintype "unspecified"))
    )
    (net (code "136") (name "R9") (class "Default")
      (node (ref "CON3") (pin "15") (pinfunction "15_15") (pintype "unspecified"))
      (node (ref "CON5") (pin "18") (pinfunction "18_18") (pintype "unspecified"))
    )
    (net (code "137") (name "R10") (class "Default")
      (node (ref "CON3") (pin "16") (pinfunction "16_16") (pintype "unspecified"))
      (node (ref "CON5") (pin "17") (pinfunction "17_17") (pintype "unspecified"))
    )
    (net (code "138") (name "R11") (class "Default")
      (node (ref "CON3") (pin "5") (pinfunction "5_5") (pintype "unspecified"))
      (node (ref "CON5") (pin "9") (pinfunction "9_9") (pintype "unspecified"))
    )
    (net (code "139") (name "R13") (class "Default")
      (node (ref "CON3") (pin "6") (pinfunction "6_6") (pintype "unspecified"))
      (node (ref "CON5") (pin "8") (pinfunction "8_8") (pintype "unspecified"))
    )
    (net (code "140") (name "T3") (class "Default")
      (node (ref "CON3") (pin "39") (pinfunction "39_39") (pintype "unspecified"))
    )
    (net (code "141") (name "T4") (class "Default")
      (node (ref "CON3") (pin "40") (pinfunction "40_40") (pintype "unspecified"))
    )
    (net (code "142") (name "T5") (class "Default")
      (node (ref "CON3") (pin "36") (pinfunction "36_36") (pintype "unspecified"))
    )
    (net (code "143") (name "T7") (class "Default")
      (node (ref "CON3") (pin "30") (pinfunction "30_30") (pintype "unspecified"))
    )
    (net (code "144") (name "T8") (class "Default")
      (node (ref "CON3") (pin "23") (pinfunction "23_23") (pintype "unspecified"))
    )
    (net (code "145") (name "T9") (class "Default")
      (node (ref "CON3") (pin "17") (pinfunction "17_17") (pintype "unspecified"))
      (node (ref "CON5") (pin "20") (pinfunction "20_20") (pintype "unspecified"))
    )
    (net (code "146") (name "T10") (class "Default")
      (node (ref "CON3") (pin "13") (pinfunction "13_13") (pintype "unspecified"))
      (node (ref "CON5") (pin "16") (pinfunction "16_16") (pintype "unspecified"))
    )
    (net (code "147") (name "T11") (class "Default")
      (node (ref "CON3") (pin "7") (pinfunction "7_7") (pintype "unspecified"))
      (node (ref "CON5") (pin "11") (pinfunction "11_11") (pintype "unspecified"))
    )
    (net (code "148") (name "T12") (class "Default")
      (node (ref "CON3") (pin "3") (pinfunction "3_3") (pintype "unspecified"))
      (node (ref "CON5") (pin "7") (pinfunction "7_7") (pintype "unspecified"))
    )
    (net (code "149") (name "T14") (class "Default")
      (node (ref "CON3") (pin "4") (pinfunction "4_4") (pintype "unspecified"))
      (node (ref "CON5") (pin "6") (pinfunction "6_6") (pintype "unspecified"))
    )
    (net (code "150") (name "V+") (class "Default")
      (node (ref "C13") (pin "1") (pinfunction "1_1") (pintype "input"))
      (node (ref "C14") (pin "1") (pinfunction "1_1") (pintype "input"))
      (node (ref "C5") (pin "1") (pinfunction "1_1") (pintype "input"))
      (node (ref "C6") (pin "1") (pinfunction "1_1") (pintype "input"))
      (node (ref "C8") (pin "2") (pinfunction "2_2") (pintype "input"))
      (node (ref "C9") (pin "2") (pinfunction "2_2") (pintype "input"))
      (node (ref "CN3") (pin "2") (pinfunction "2_2") (pintype "unspecified"))
      (node (ref "CN4") (pin "5") (pinfunction "5_5") (pintype "unspecified"))
      (node (ref "DC2") (pin "1") (pinfunction "IN_1") (pintype "unspecified"))
      (node (ref "R19") (pin "2") (pinfunction "2_2") (pintype "input"))
      (node (ref "R21") (pin "2") (pinfunction "2_2") (pintype "input"))
      (node (ref "R22") (pin "1") (pinfunction "1_1") (pintype "input"))
      (node (ref "U1") (pin "5") (pinfunction "VIN_5") (pintype "input"))
    )
    (net (code "151") (name "VCC") (class "Default")
      (node (ref "C3") (pin "1") (pinfunction "1_1") (pintype "input"))
      (node (ref "C4") (pin "1") (pinfunction "1_1") (pintype "input"))
      (node (ref "CN3") (pin "3") (pinfunction "3_3") (pintype "unspecified"))
      (node (ref "CN4") (pin "4") (pinfunction "4_4") (pintype "unspecified"))
      (node (ref "CON5") (pin "4") (pinfunction "4_4") (pintype "unspecified"))
      (node (ref "CON5") (pin "5") (pinfunction "5_5") (pintype "unspecified"))
      (node (ref "DC1") (pin "3") (pinfunction "OUT_3") (pintype "unspecified"))
      (node (ref "H2") (pin "1") (pinfunction "1_1") (pintype "input"))
      (node (ref "H5") (pin "6") (pinfunction "6_6") (pintype "input"))
      (node (ref "R10") (pin "1") (pinfunction "1_1") (pintype "input"))
      (node (ref "R11") (pin "1") (pinfunction "1_1") (pintype "input"))
      (node (ref "R12") (pin "1") (pinfunction "1_1") (pintype "input"))
      (node (ref "R13") (pin "1") (pinfunction "1_1") (pintype "input"))
      (node (ref "R14") (pin "1") (pinfunction "1_1") (pintype "input"))
      (node (ref "R15") (pin "1") (pinfunction "1_1") (pintype "input"))
      (node (ref "R16") (pin "1") (pinfunction "1_1") (pintype "input"))
      (node (ref "R17") (pin "1") (pinfunction "1_1") (pintype "input"))
      (node (ref "R20") (pin "2") (pinfunction "2_2") (pintype "input"))
      (node (ref "R9") (pin "1") (pinfunction "1_1") (pintype "input"))
    )
    (net (code "152") (name "unconnected-(CON5-Pad41)") (class "Default")
      (node (ref "CON5") (pin "41") (pinfunction "41_41") (pintype "unspecified"))
    )
    (net (code "153") (name "unconnected-(CON5-Pad42)") (class "Default")
      (node (ref "CON5") (pin "42") (pinfunction "42_42") (pintype "unspecified"))
    )
    (net (code "154") (name "unconnected-(H2-Pad2)") (class "Default")
      (node (ref "H2") (pin "2") (pinfunction "2_2") (pintype "input"))
    )
    (net (code "155") (name "unconnected-(H2-Pad3)") (class "Default")
      (node (ref "H2") (pin "3") (pinfunction "3_3") (pintype "input"))
    )
    (net (code "156") (name "unconnected-(H2-Pad4)") (class "Default")
      (node (ref "H2") (pin "4") (pinfunction "4_4") (pintype "input"))
    )
    (net (code "157") (name "unconnected-(H2-Pad5)") (class "Default")
      (node (ref "H2") (pin "5") (pinfunction "5_5") (pintype "input"))
    )
    (net (code "158") (name "unconnected-(H2-Pad6)") (class "Default")
      (node (ref "H2") (pin "6") (pinfunction "6_6") (pintype "input"))
    )
    (net (code "159") (name "unconnected-(H2-Pad7)") (class "Default")
      (node (ref "H2") (pin "7") (pinfunction "7_7") (pintype "input"))
    )
    (net (code "160") (name "unconnected-(H2-Pad8)") (class "Default")
      (node (ref "H2") (pin "8") (pinfunction "8_8") (pintype "input"))
    )
  )
)
